# 32_bit_buffered_shift_register.net
KiCad netlist of a schematic drawn in EAGLE
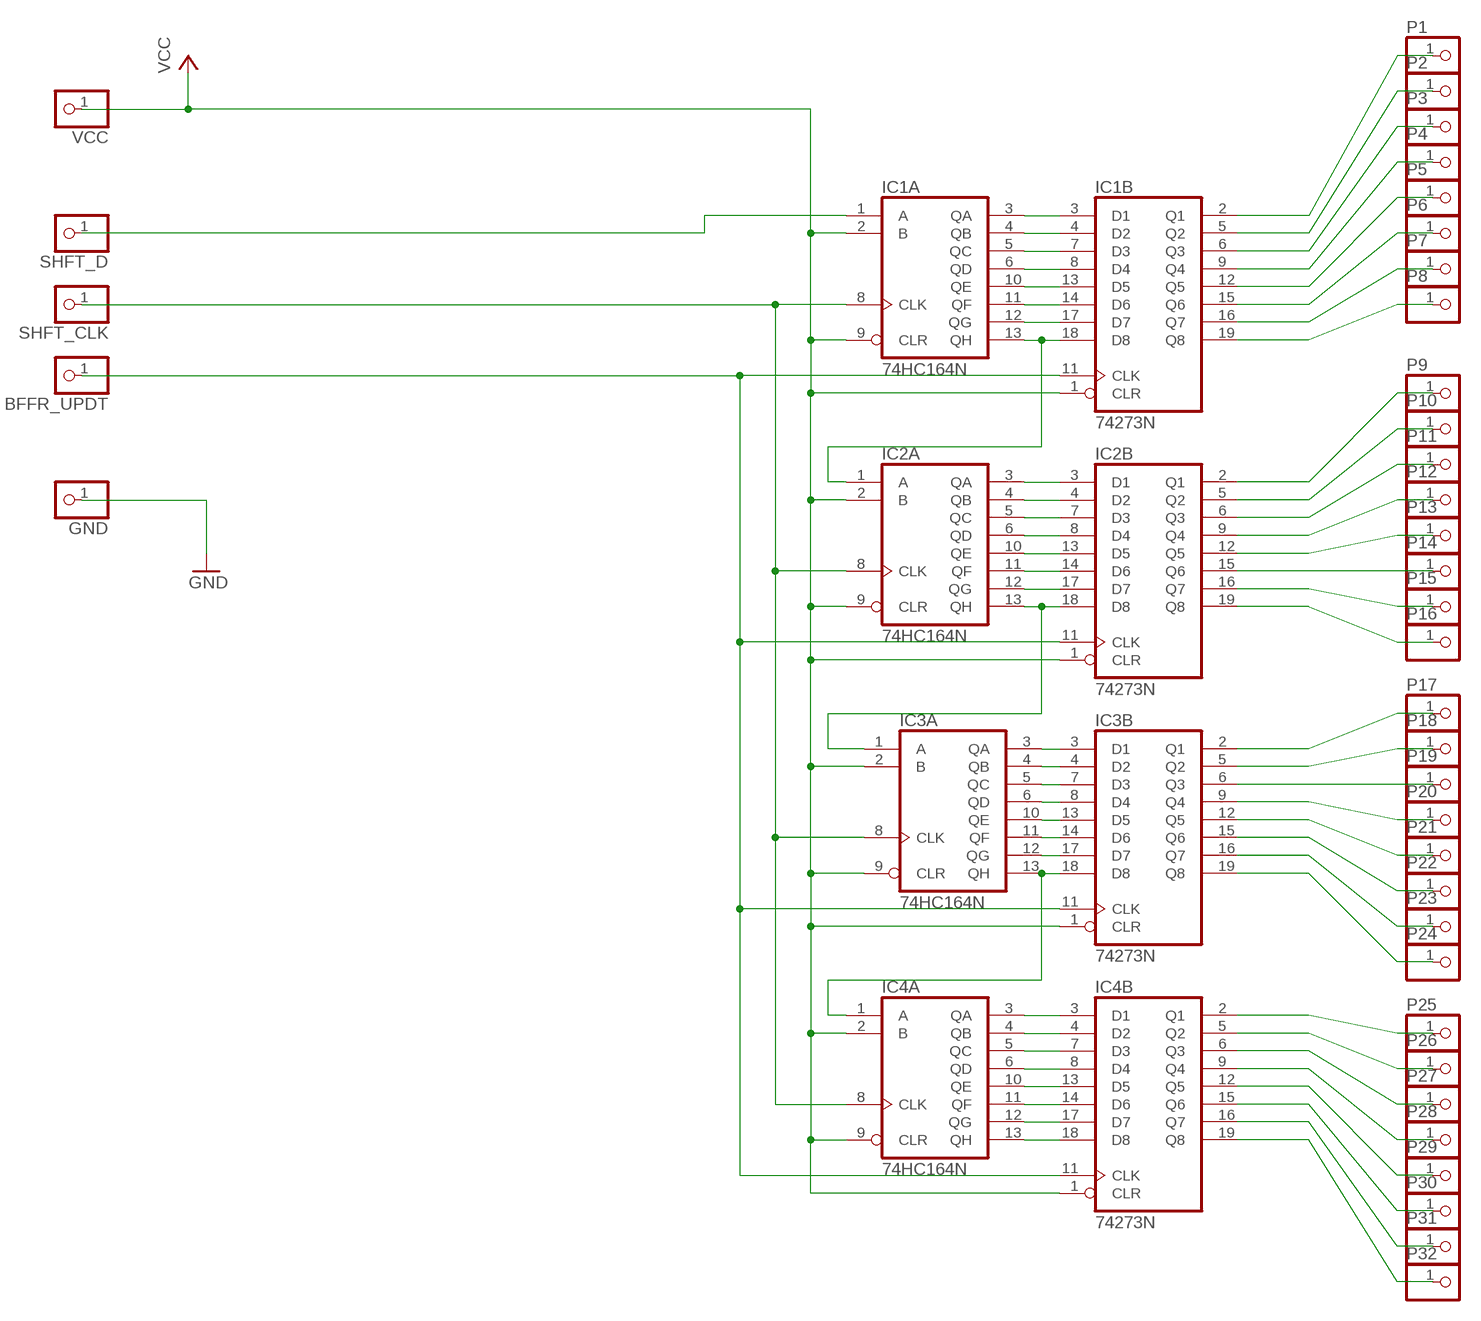
[diagram p0: schematic, sheet 1]

(export (version "E")
  (design (tool "Eeschema 10.0.6"))
  (components
    (comp (ref "BFFR_UPDT")
      (value "PINHD-1X1")
      (footprint "eagle-import:1X01")
      (libsource (lib "eagle-import") (part "PINHD-1X1"))
    )
    (comp (ref "GND")
      (value "PINHD-1X1")
      (footprint "eagle-import:1X01")
      (libsource (lib "eagle-import") (part "PINHD-1X1"))
    )
    (comp (ref "IC1A")
      (value "74HC164N")
      (footprint "eagle-import:DIL14")
      (libsource (lib "eagle-import") (part "74164NHC"))
    )
    (comp (ref "IC1B")
      (value "74273N")
      (footprint "eagle-import:DIL20")
      (libsource (lib "eagle-import") (part "74273N"))
    )
    (comp (ref "IC2A")
      (value "74HC164N")
      (footprint "eagle-import:DIL14")
      (libsource (lib "eagle-import") (part "74164NHC"))
    )
    (comp (ref "IC2B")
      (value "74273N")
      (footprint "eagle-import:DIL20")
      (libsource (lib "eagle-import") (part "74273N"))
    )
    (comp (ref "IC3A")
      (value "74HC164N")
      (footprint "eagle-import:DIL14")
      (libsource (lib "eagle-import") (part "74164NHC"))
    )
    (comp (ref "IC3B")
      (value "74273N")
      (footprint "eagle-import:DIL20")
      (libsource (lib "eagle-import") (part "74273N"))
    )
    (comp (ref "IC4A")
      (value "74HC164N")
      (footprint "eagle-import:DIL14")
      (libsource (lib "eagle-import") (part "74164NHC"))
    )
    (comp (ref "IC4B")
      (value "74273N")
      (footprint "eagle-import:DIL20")
      (libsource (lib "eagle-import") (part "74273N"))
    )
    (comp (ref "P1")
      (value "PINHD-1X1")
      (footprint "eagle-import:1X01")
      (libsource (lib "eagle-import") (part "PINHD-1X1"))
    )
    (comp (ref "P2")
      (value "PINHD-1X1")
      (footprint "eagle-import:1X01")
      (libsource (lib "eagle-import") (part "PINHD-1X1"))
    )
    (comp (ref "P3")
      (value "PINHD-1X1")
      (footprint "eagle-import:1X01")
      (libsource (lib "eagle-import") (part "PINHD-1X1"))
    )
    (comp (ref "P4")
      (value "PINHD-1X1")
      (footprint "eagle-import:1X01")
      (libsource (lib "eagle-import") (part "PINHD-1X1"))
    )
    (comp (ref "P5")
      (value "PINHD-1X1")
      (footprint "eagle-import:1X01")
      (libsource (lib "eagle-import") (part "PINHD-1X1"))
    )
    (comp (ref "P6")
      (value "PINHD-1X1")
      (footprint "eagle-import:1X01")
      (libsource (lib "eagle-import") (part "PINHD-1X1"))
    )
    (comp (ref "P7")
      (value "PINHD-1X1")
      (footprint "eagle-import:1X01")
      (libsource (lib "eagle-import") (part "PINHD-1X1"))
    )
    (comp (ref "P8")
      (value "PINHD-1X1")
      (footprint "eagle-import:1X01")
      (libsource (lib "eagle-import") (part "PINHD-1X1"))
    )
    (comp (ref "P9")
      (value "PINHD-1X1")
      (footprint "eagle-import:1X01")
      (libsource (lib "eagle-import") (part "PINHD-1X1"))
    )
    (comp (ref "P10")
      (value "PINHD-1X1")
      (footprint "eagle-import:1X01")
      (libsource (lib "eagle-import") (part "PINHD-1X1"))
    )
    (comp (ref "P11")
      (value "PINHD-1X1")
      (footprint "eagle-import:1X01")
      (libsource (lib "eagle-import") (part "PINHD-1X1"))
    )
    (comp (ref "P12")
      (value "PINHD-1X1")
      (footprint "eagle-import:1X01")
      (libsource (lib "eagle-import") (part "PINHD-1X1"))
    )
    (comp (ref "P13")
      (value "PINHD-1X1")
      (footprint "eagle-import:1X01")
      (libsource (lib "eagle-import") (part "PINHD-1X1"))
    )
    (comp (ref "P14")
      (value "PINHD-1X1")
      (footprint "eagle-import:1X01")
      (libsource (lib "eagle-import") (part "PINHD-1X1"))
    )
    (comp (ref "P15")
      (value "PINHD-1X1")
      (footprint "eagle-import:1X01")
      (libsource (lib "eagle-import") (part "PINHD-1X1"))
    )
    (comp (ref "P16")
      (value "PINHD-1X1")
      (footprint "eagle-import:1X01")
      (libsource (lib "eagle-import") (part "PINHD-1X1"))
    )
    (comp (ref "P17")
      (value "PINHD-1X1")
      (footprint "eagle-import:1X01")
      (libsource (lib "eagle-import") (part "PINHD-1X1"))
    )
    (comp (ref "P18")
      (value "PINHD-1X1")
      (footprint "eagle-import:1X01")
      (libsource (lib "eagle-import") (part "PINHD-1X1"))
    )
    (comp (ref "P19")
      (value "PINHD-1X1")
      (footprint "eagle-import:1X01")
      (libsource (lib "eagle-import") (part "PINHD-1X1"))
    )
    (comp (ref "P20")
      (value "PINHD-1X1")
      (footprint "eagle-import:1X01")
      (libsource (lib "eagle-import") (part "PINHD-1X1"))
    )
    (comp (ref "P21")
      (value "PINHD-1X1")
      (footprint "eagle-import:1X01")
      (libsource (lib "eagle-import") (part "PINHD-1X1"))
    )
    (comp (ref "P22")
      (value "PINHD-1X1")
      (footprint "eagle-import:1X01")
      (libsource (lib "eagle-import") (part "PINHD-1X1"))
    )
    (comp (ref "P23")
      (value "PINHD-1X1")
      (footprint "eagle-import:1X01")
      (libsource (lib "eagle-import") (part "PINHD-1X1"))
    )
    (comp (ref "P24")
      (value "PINHD-1X1")
      (footprint "eagle-import:1X01")
      (libsource (lib "eagle-import") (part "PINHD-1X1"))
    )
    (comp (ref "P25")
      (value "PINHD-1X1")
      (footprint "eagle-import:1X01")
      (libsource (lib "eagle-import") (part "PINHD-1X1"))
    )
    (comp (ref "P26")
      (value "PINHD-1X1")
      (footprint "eagle-import:1X01")
      (libsource (lib "eagle-import") (part "PINHD-1X1"))
    )
    (comp (ref "P27")
      (value "PINHD-1X1")
      (footprint "eagle-import:1X01")
      (libsource (lib "eagle-import") (part "PINHD-1X1"))
    )
    (comp (ref "P28")
      (value "PINHD-1X1")
      (footprint "eagle-import:1X01")
      (libsource (lib "eagle-import") (part "PINHD-1X1"))
    )
    (comp (ref "P29")
      (value "PINHD-1X1")
      (footprint "eagle-import:1X01")
      (libsource (lib "eagle-import") (part "PINHD-1X1"))
    )
    (comp (ref "P30")
      (value "PINHD-1X1")
      (footprint "eagle-import:1X01")
      (libsource (lib "eagle-import") (part "PINHD-1X1"))
    )
    (comp (ref "P31")
      (value "PINHD-1X1")
      (footprint "eagle-import:1X01")
      (libsource (lib "eagle-import") (part "PINHD-1X1"))
    )
    (comp (ref "P32")
      (value "PINHD-1X1")
      (footprint "eagle-import:1X01")
      (libsource (lib "eagle-import") (part "PINHD-1X1"))
    )
    (comp (ref "SHFT_CLK")
      (value "PINHD-1X1")
      (footprint "eagle-import:1X01")
      (libsource (lib "eagle-import") (part "PINHD-1X1"))
    )
    (comp (ref "SHFT_D")
      (value "PINHD-1X1")
      (footprint "eagle-import:1X01")
      (libsource (lib "eagle-import") (part "PINHD-1X1"))
    )
    (comp (ref "VCC")
      (value "PINHD-1X1")
      (footprint "eagle-import:1X01")
      (libsource (lib "eagle-import") (part "PINHD-1X1"))
    )
  )
  (nets
    (net (code "1") (name "GND") (class "Default")
      (node (ref "GND") (pin "1") (pinfunction "1_1") (pintype "passive"))
    )
    (net (code "2") (name "Net-(IC1AA-A)") (class "Default")
      (node (ref "IC1A") (pin "1") (pinfunction "A_1") (pintype "input"))
      (node (ref "SHFT_D") (pin "1") (pinfunction "1_1") (pintype "passive"))
    )
    (net (code "3") (name "Net-(IC1AA-CLK)") (class "Default")
      (node (ref "IC1A") (pin "8") (pinfunction "CLK_8") (pintype "input"))
      (node (ref "IC2A") (pin "8") (pinfunction "CLK_8") (pintype "input"))
      (node (ref "IC3A") (pin "8") (pinfunction "CLK_8") (pintype "input"))
      (node (ref "IC4A") (pin "8") (pinfunction "CLK_8") (pintype "input"))
      (node (ref "SHFT_CLK") (pin "1") (pinfunction "1_1") (pintype "passive"))
    )
    (net (code "4") (name "Net-(IC1AA-QA)") (class "Default")
      (node (ref "IC1A") (pin "3") (pinfunction "QA_3") (pintype "output"))
      (node (ref "IC1B") (pin "3") (pinfunction "D1_3") (pintype "input"))
    )
    (net (code "5") (name "Net-(IC1AA-QB)") (class "Default")
      (node (ref "IC1A") (pin "4") (pinfunction "QB_4") (pintype "output"))
      (node (ref "IC1B") (pin "4") (pinfunction "D2_4") (pintype "input"))
    )
    (net (code "6") (name "Net-(IC1AA-QC)") (class "Default")
      (node (ref "IC1A") (pin "5") (pinfunction "QC_5") (pintype "output"))
      (node (ref "IC1B") (pin "7") (pinfunction "D3_7") (pintype "input"))
    )
    (net (code "7") (name "Net-(IC1AA-QD)") (class "Default")
      (node (ref "IC1A") (pin "6") (pinfunction "QD_6") (pintype "output"))
      (node (ref "IC1B") (pin "8") (pinfunction "D4_8") (pintype "input"))
    )
    (net (code "8") (name "Net-(IC1AA-QE)") (class "Default")
      (node (ref "IC1A") (pin "10") (pinfunction "QE_10") (pintype "output"))
      (node (ref "IC1B") (pin "13") (pinfunction "D5_13") (pintype "input"))
    )
    (net (code "9") (name "Net-(IC1AA-QF)") (class "Default")
      (node (ref "IC1A") (pin "11") (pinfunction "QF_11") (pintype "output"))
      (node (ref "IC1B") (pin "14") (pinfunction "D6_14") (pintype "input"))
    )
    (net (code "10") (name "Net-(IC1AA-QG)") (class "Default")
      (node (ref "IC1A") (pin "12") (pinfunction "QG_12") (pintype "output"))
      (node (ref "IC1B") (pin "17") (pinfunction "D7_17") (pintype "input"))
    )
    (net (code "11") (name "Net-(IC1AA-QH)") (class "Default")
      (node (ref "IC1A") (pin "13") (pinfunction "QH_13") (pintype "output"))
      (node (ref "IC1B") (pin "18") (pinfunction "D8_18") (pintype "input"))
      (node (ref "IC2A") (pin "1") (pinfunction "A_1") (pintype "input"))
    )
    (net (code "12") (name "Net-(IC1BA-CLK)") (class "Default")
      (node (ref "BFFR_UPDT") (pin "1") (pinfunction "1_1") (pintype "passive"))
      (node (ref "IC1B") (pin "11") (pinfunction "CLK_11") (pintype "input"))
      (node (ref "IC2B") (pin "11") (pinfunction "CLK_11") (pintype "input"))
      (node (ref "IC3B") (pin "11") (pinfunction "CLK_11") (pintype "input"))
      (node (ref "IC4B") (pin "11") (pinfunction "CLK_11") (pintype "input"))
    )
    (net (code "13") (name "Net-(IC1BA-Q1)") (class "Default")
      (node (ref "IC1B") (pin "2") (pinfunction "Q1_2") (pintype "output"))
      (node (ref "P1") (pin "1") (pinfunction "1_1") (pintype "passive"))
    )
    (net (code "14") (name "Net-(IC1BA-Q2)") (class "Default")
      (node (ref "IC1B") (pin "5") (pinfunction "Q2_5") (pintype "output"))
      (node (ref "P2") (pin "1") (pinfunction "1_1") (pintype "passive"))
    )
    (net (code "15") (name "Net-(IC1BA-Q3)") (class "Default")
      (node (ref "IC1B") (pin "6") (pinfunction "Q3_6") (pintype "output"))
      (node (ref "P3") (pin "1") (pinfunction "1_1") (pintype "passive"))
    )
    (net (code "16") (name "Net-(IC1BA-Q4)") (class "Default")
      (node (ref "IC1B") (pin "9") (pinfunction "Q4_9") (pintype "output"))
      (node (ref "P4") (pin "1") (pinfunction "1_1") (pintype "passive"))
    )
    (net (code "17") (name "Net-(IC1BA-Q5)") (class "Default")
      (node (ref "IC1B") (pin "12") (pinfunction "Q5_12") (pintype "output"))
      (node (ref "P5") (pin "1") (pinfunction "1_1") (pintype "passive"))
    )
    (net (code "18") (name "Net-(IC1BA-Q6)") (class "Default")
      (node (ref "IC1B") (pin "15") (pinfunction "Q6_15") (pintype "output"))
      (node (ref "P6") (pin "1") (pinfunction "1_1") (pintype "passive"))
    )
    (net (code "19") (name "Net-(IC1BA-Q7)") (class "Default")
      (node (ref "IC1B") (pin "16") (pinfunction "Q7_16") (pintype "output"))
      (node (ref "P7") (pin "1") (pinfunction "1_1") (pintype "passive"))
    )
    (net (code "20") (name "Net-(IC1BA-Q8)") (class "Default")
      (node (ref "IC1B") (pin "19") (pinfunction "Q8_19") (pintype "output"))
      (node (ref "P8") (pin "1") (pinfunction "1_1") (pintype "passive"))
    )
    (net (code "21") (name "Net-(IC2AA-QA)") (class "Default")
      (node (ref "IC2A") (pin "3") (pinfunction "QA_3") (pintype "output"))
      (node (ref "IC2B") (pin "3") (pinfunction "D1_3") (pintype "input"))
    )
    (net (code "22") (name "Net-(IC2AA-QB)") (class "Default")
      (node (ref "IC2A") (pin "4") (pinfunction "QB_4") (pintype "output"))
      (node (ref "IC2B") (pin "4") (pinfunction "D2_4") (pintype "input"))
    )
    (net (code "23") (name "Net-(IC2AA-QC)") (class "Default")
      (node (ref "IC2A") (pin "5") (pinfunction "QC_5") (pintype "output"))
      (node (ref "IC2B") (pin "7") (pinfunction "D3_7") (pintype "input"))
    )
    (net (code "24") (name "Net-(IC2AA-QD)") (class "Default")
      (node (ref "IC2A") (pin "6") (pinfunction "QD_6") (pintype "output"))
      (node (ref "IC2B") (pin "8") (pinfunction "D4_8") (pintype "input"))
    )
    (net (code "25") (name "Net-(IC2AA-QE)") (class "Default")
      (node (ref "IC2A") (pin "10") (pinfunction "QE_10") (pintype "output"))
      (node (ref "IC2B") (pin "13") (pinfunction "D5_13") (pintype "input"))
    )
    (net (code "26") (name "Net-(IC2AA-QF)") (class "Default")
      (node (ref "IC2A") (pin "11") (pinfunction "QF_11") (pintype "output"))
      (node (ref "IC2B") (pin "14") (pinfunction "D6_14") (pintype "input"))
    )
    (net (code "27") (name "Net-(IC2AA-QG)") (class "Default")
      (node (ref "IC2A") (pin "12") (pinfunction "QG_12") (pintype "output"))
      (node (ref "IC2B") (pin "17") (pinfunction "D7_17") (pintype "input"))
    )
    (net (code "28") (name "Net-(IC2AA-QH)") (class "Default")
      (node (ref "IC2A") (pin "13") (pinfunction "QH_13") (pintype "output"))
      (node (ref "IC2B") (pin "18") (pinfunction "D8_18") (pintype "input"))
      (node (ref "IC3A") (pin "1") (pinfunction "A_1") (pintype "input"))
    )
    (net (code "29") (name "Net-(IC2BA-Q1)") (class "Default")
      (node (ref "IC2B") (pin "2") (pinfunction "Q1_2") (pintype "output"))
      (node (ref "P9") (pin "1") (pinfunction "1_1") (pintype "passive"))
    )
    (net (code "30") (name "Net-(IC2BA-Q2)") (class "Default")
      (node (ref "IC2B") (pin "5") (pinfunction "Q2_5") (pintype "output"))
      (node (ref "P10") (pin "1") (pinfunction "1_1") (pintype "passive"))
    )
    (net (code "31") (name "Net-(IC2BA-Q3)") (class "Default")
      (node (ref "IC2B") (pin "6") (pinfunction "Q3_6") (pintype "output"))
      (node (ref "P11") (pin "1") (pinfunction "1_1") (pintype "passive"))
    )
    (net (code "32") (name "Net-(IC2BA-Q4)") (class "Default")
      (node (ref "IC2B") (pin "9") (pinfunction "Q4_9") (pintype "output"))
      (node (ref "P12") (pin "1") (pinfunction "1_1") (pintype "passive"))
    )
    (net (code "33") (name "Net-(IC2BA-Q5)") (class "Default")
      (node (ref "IC2B") (pin "12") (pinfunction "Q5_12") (pintype "output"))
      (node (ref "P13") (pin "1") (pinfunction "1_1") (pintype "passive"))
    )
    (net (code "34") (name "Net-(IC2BA-Q6)") (class "Default")
      (node (ref "IC2B") (pin "15") (pinfunction "Q6_15") (pintype "output"))
      (node (ref "P14") (pin "1") (pinfunction "1_1") (pintype "passive"))
    )
    (net (code "35") (name "Net-(IC2BA-Q7)") (class "Default")
      (node (ref "IC2B") (pin "16") (pinfunction "Q7_16") (pintype "output"))
      (node (ref "P15") (pin "1") (pinfunction "1_1") (pintype "passive"))
    )
    (net (code "36") (name "Net-(IC2BA-Q8)") (class "Default")
      (node (ref "IC2B") (pin "19") (pinfunction "Q8_19") (pintype "output"))
      (node (ref "P16") (pin "1") (pinfunction "1_1") (pintype "passive"))
    )
    (net (code "37") (name "Net-(IC3AA-QA)") (class "Default")
      (node (ref "IC3A") (pin "3") (pinfunction "QA_3") (pintype "output"))
      (node (ref "IC3B") (pin "3") (pinfunction "D1_3") (pintype "input"))
    )
    (net (code "38") (name "Net-(IC3AA-QB)") (class "Default")
      (node (ref "IC3A") (pin "4") (pinfunction "QB_4") (pintype "output"))
      (node (ref "IC3B") (pin "4") (pinfunction "D2_4") (pintype "input"))
    )
    (net (code "39") (name "Net-(IC3AA-QC)") (class "Default")
      (node (ref "IC3A") (pin "5") (pinfunction "QC_5") (pintype "output"))
      (node (ref "IC3B") (pin "7") (pinfunction "D3_7") (pintype "input"))
    )
    (net (code "40") (name "Net-(IC3AA-QD)") (class "Default")
      (node (ref "IC3A") (pin "6") (pinfunction "QD_6") (pintype "output"))
      (node (ref "IC3B") (pin "8") (pinfunction "D4_8") (pintype "input"))
    )
    (net (code "41") (name "Net-(IC3AA-QE)") (class "Default")
      (node (ref "IC3A") (pin "10") (pinfunction "QE_10") (pintype "output"))
      (node (ref "IC3B") (pin "13") (pinfunction "D5_13") (pintype "input"))
    )
    (net (code "42") (name "Net-(IC3AA-QF)") (class "Default")
      (node (ref "IC3A") (pin "11") (pinfunction "QF_11") (pintype "output"))
      (node (ref "IC3B") (pin "14") (pinfunction "D6_14") (pintype "input"))
    )
    (net (code "43") (name "Net-(IC3AA-QG)") (class "Default")
      (node (ref "IC3A") (pin "12") (pinfunction "QG_12") (pintype "output"))
      (node (ref "IC3B") (pin "17") (pinfunction "D7_17") (pintype "input"))
    )
    (net (code "44") (name "Net-(IC3AA-QH)") (class "Default")
      (node (ref "IC3A") (pin "13") (pinfunction "QH_13") (pintype "output"))
      (node (ref "IC3B") (pin "18") (pinfunction "D8_18") (pintype "input"))
      (node (ref "IC4A") (pin "1") (pinfunction "A_1") (pintype "input"))
    )
    (net (code "45") (name "Net-(IC3BA-Q1)") (class "Default")
      (node (ref "IC3B") (pin "2") (pinfunction "Q1_2") (pintype "output"))
      (node (ref "P17") (pin "1") (pinfunction "1_1") (pintype "passive"))
    )
    (net (code "46") (name "Net-(IC3BA-Q2)") (class "Default")
      (node (ref "IC3B") (pin "5") (pinfunction "Q2_5") (pintype "output"))
      (node (ref "P18") (pin "1") (pinfunction "1_1") (pintype "passive"))
    )
    (net (code "47") (name "Net-(IC3BA-Q3)") (class "Default")
      (node (ref "IC3B") (pin "6") (pinfunction "Q3_6") (pintype "output"))
      (node (ref "P19") (pin "1") (pinfunction "1_1") (pintype "passive"))
    )
    (net (code "48") (name "Net-(IC3BA-Q4)") (class "Default")
      (node (ref "IC3B") (pin "9") (pinfunction "Q4_9") (pintype "output"))
      (node (ref "P20") (pin "1") (pinfunction "1_1") (pintype "passive"))
    )
    (net (code "49") (name "Net-(IC3BA-Q5)") (class "Default")
      (node (ref "IC3B") (pin "12") (pinfunction "Q5_12") (pintype "output"))
      (node (ref "P21") (pin "1") (pinfunction "1_1") (pintype "passive"))
    )
    (net (code "50") (name "Net-(IC3BA-Q6)") (class "Default")
      (node (ref "IC3B") (pin "15") (pinfunction "Q6_15") (pintype "output"))
      (node (ref "P22") (pin "1") (pinfunction "1_1") (pintype "passive"))
    )
    (net (code "51") (name "Net-(IC3BA-Q7)") (class "Default")
      (node (ref "IC3B") (pin "16") (pinfunction "Q7_16") (pintype "output"))
      (node (ref "P23") (pin "1") (pinfunction "1_1") (pintype "passive"))
    )
    (net (code "52") (name "Net-(IC3BA-Q8)") (class "Default")
      (node (ref "IC3B") (pin "19") (pinfunction "Q8_19") (pintype "output"))
      (node (ref "P24") (pin "1") (pinfunction "1_1") (pintype "passive"))
    )
    (net (code "53") (name "Net-(IC4AA-QA)") (class "Default")
      (node (ref "IC4A") (pin "3") (pinfunction "QA_3") (pintype "output"))
      (node (ref "IC4B") (pin "3") (pinfunction "D1_3") (pintype "input"))
    )
    (net (code "54") (name "Net-(IC4AA-QB)") (class "Default")
      (node (ref "IC4A") (pin "4") (pinfunction "QB_4") (pintype "output"))
      (node (ref "IC4B") (pin "4") (pinfunction "D2_4") (pintype "input"))
    )
    (net (code "55") (name "Net-(IC4AA-QC)") (class "Default")
      (node (ref "IC4A") (pin "5") (pinfunction "QC_5") (pintype "output"))
      (node (ref "IC4B") (pin "7") (pinfunction "D3_7") (pintype "input"))
    )
    (net (code "56") (name "Net-(IC4AA-QD)") (class "Default")
      (node (ref "IC4A") (pin "6") (pinfunction "QD_6") (pintype "output"))
      (node (ref "IC4B") (pin "8") (pinfunction "D4_8") (pintype "input"))
    )
    (net (code "57") (name "Net-(IC4AA-QE)") (class "Default")
      (node (ref "IC4A") (pin "10") (pinfunction "QE_10") (pintype "output"))
      (node (ref "IC4B") (pin "13") (pinfunction "D5_13") (pintype "input"))
    )
    (net (code "58") (name "Net-(IC4AA-QF)") (class "Default")
      (node (ref "IC4A") (pin "11") (pinfunction "QF_11") (pintype "output"))
      (node (ref "IC4B") (pin "14") (pinfunction "D6_14") (pintype "input"))
    )
    (net (code "59") (name "Net-(IC4AA-QG)") (class "Default")
      (node (ref "IC4A") (pin "12") (pinfunction "QG_12") (pintype "output"))
      (node (ref "IC4B") (pin "17") (pinfunction "D7_17") (pintype "input"))
    )
    (net (code "60") (name "Net-(IC4AA-QH)") (class "Default")
      (node (ref "IC4A") (pin "13") (pinfunction "QH_13") (pintype "output"))
      (node (ref "IC4B") (pin "18") (pinfunction "D8_18") (pintype "input"))
    )
    (net (code "61") (name "Net-(IC4BA-Q1)") (class "Default")
      (node (ref "IC4B") (pin "2") (pinfunction "Q1_2") (pintype "output"))
      (node (ref "P25") (pin "1") (pinfunction "1_1") (pintype "passive"))
    )
    (net (code "62") (name "Net-(IC4BA-Q2)") (class "Default")
      (node (ref "IC4B") (pin "5") (pinfunction "Q2_5") (pintype "output"))
      (node (ref "P26") (pin "1") (pinfunction "1_1") (pintype "passive"))
    )
    (net (code "63") (name "Net-(IC4BA-Q3)") (class "Default")
      (node (ref "IC4B") (pin "6") (pinfunction "Q3_6") (pintype "output"))
      (node (ref "P27") (pin "1") (pinfunction "1_1") (pintype "passive"))
    )
    (net (code "64") (name "Net-(IC4BA-Q4)") (class "Default")
      (node (ref "IC4B") (pin "9") (pinfunction "Q4_9") (pintype "output"))
      (node (ref "P28") (pin "1") (pinfunction "1_1") (pintype "passive"))
    )
    (net (code "65") (name "Net-(IC4BA-Q5)") (class "Default")
      (node (ref "IC4B") (pin "12") (pinfunction "Q5_12") (pintype "output"))
      (node (ref "P29") (pin "1") (pinfunction "1_1") (pintype "passive"))
    )
    (net (code "66") (name "Net-(IC4BA-Q6)") (class "Default")
      (node (ref "IC4B") (pin "15") (pinfunction "Q6_15") (pintype "output"))
      (node (ref "P30") (pin "1") (pinfunction "1_1") (pintype "passive"))
    )
    (net (code "67") (name "Net-(IC4BA-Q7)") (class "Default")
      (node (ref "IC4B") (pin "16") (pinfunction "Q7_16") (pintype "output"))
      (node (ref "P31") (pin "1") (pinfunction "1_1") (pintype "passive"))
    )
    (net (code "68") (name "Net-(IC4BA-Q8)") (class "Default")
      (node (ref "IC4B") (pin "19") (pinfunction "Q8_19") (pintype "output"))
      (node (ref "P32") (pin "1") (pinfunction "1_1") (pintype "passive"))
    )
    (net (code "69") (name "VCC") (class "Default")
      (node (ref "IC1A") (pin "2") (pinfunction "B_2") (pintype "input"))
      (node (ref "IC1A") (pin "9") (pinfunction "CLR_9") (pintype "input"))
      (node (ref "IC1B") (pin "1") (pinfunction "CLR_1") (pintype "input"))
      (node (ref "IC2A") (pin "2") (pinfunction "B_2") (pintype "input"))
      (node (ref "IC2A") (pin "9") (pinfunction "CLR_9") (pintype "input"))
      (node (ref "IC2B") (pin "1") (pinfunction "CLR_1") (pintype "input"))
      (node (ref "IC3A") (pin "2") (pinfunction "B_2") (pintype "input"))
      (node (ref "IC3A") (pin "9") (pinfunction "CLR_9") (pintype "input"))
      (node (ref "IC3B") (pin "1") (pinfunction "CLR_1") (pintype "input"))
      (node (ref "IC4A") (pin "2") (pinfunction "B_2") (pintype "input"))
      (node (ref "IC4A") (pin "9") (pinfunction "CLR_9") (pintype "input"))
      (node (ref "IC4B") (pin "1") (pinfunction "CLR_1") (pintype "input"))
      (node (ref "VCC") (pin "1") (pinfunction "1_1") (pintype "passive"))
    )
  )
)
